# ANET3D-ISP-Adapter.net
KiCad netlist of a schematic drawn in EAGLE
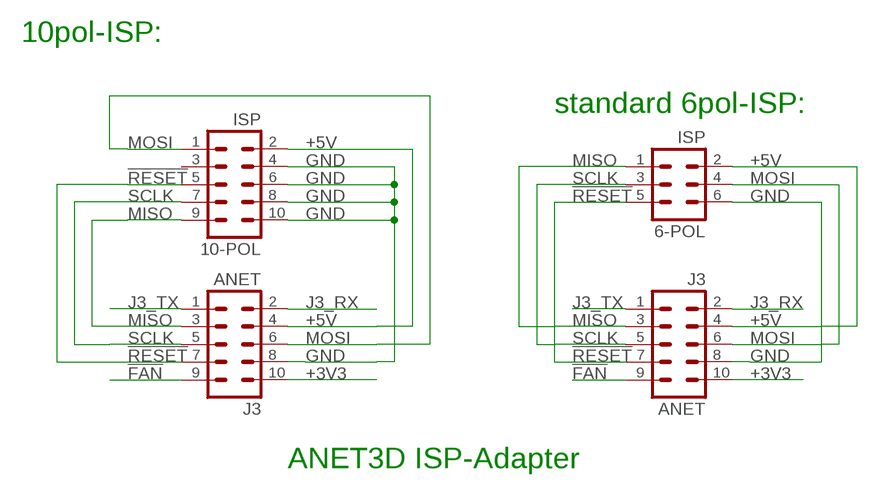
[diagram p0: schematic, sheet 1]

(export (version "E")
  (design (tool "Eeschema 10.0.6"))
  (components
    (comp (ref "6-POL")
      (value "ISP")
      (footprint "eagle-import:ML6")
      (libsource (lib "eagle-import") (part "ML6"))
    )
    (comp (ref "10-POL")
      (value "ISP")
      (footprint "eagle-import:ML10")
      (libsource (lib "eagle-import") (part "ML10"))
    )
    (comp (ref "ANET")
      (value "J3")
      (footprint "eagle-import:ML10")
      (libsource (lib "eagle-import") (part "ML10"))
    )
    (comp (ref "J3")
      (value "ANET")
      (footprint "eagle-import:ML10")
      (libsource (lib "eagle-import") (part "ML10"))
    )
  )
  (nets
    (net (code "1") (name "/+3V3") (class "Default")
      (node (ref "ANET") (pin "10") (pinfunction "10_10") (pintype "passive"))
      (node (ref "J3") (pin "10") (pinfunction "10_10") (pintype "passive"))
    )
    (net (code "2") (name "/+5V") (class "Default")
      (node (ref "10-POL") (pin "2") (pinfunction "2_2") (pintype "passive"))
      (node (ref "6-POL") (pin "2") (pinfunction "2_2") (pintype "passive"))
      (node (ref "ANET") (pin "4") (pinfunction "4_4") (pintype "passive"))
      (node (ref "J3") (pin "4") (pinfunction "4_4") (pintype "passive"))
    )
    (net (code "3") (name "/GND") (class "Default")
      (node (ref "10-POL") (pin "10") (pinfunction "10_10") (pintype "passive"))
      (node (ref "10-POL") (pin "4") (pinfunction "4_4") (pintype "passive"))
      (node (ref "10-POL") (pin "6") (pinfunction "6_6") (pintype "passive"))
      (node (ref "10-POL") (pin "8") (pinfunction "8_8") (pintype "passive"))
      (node (ref "6-POL") (pin "6") (pinfunction "6_6") (pintype "passive"))
      (node (ref "ANET") (pin "8") (pinfunction "8_8") (pintype "passive"))
      (node (ref "J3") (pin "8") (pinfunction "8_8") (pintype "passive"))
    )
    (net (code "4") (name "/J3_RX") (class "Default")
      (node (ref "ANET") (pin "2") (pinfunction "2_2") (pintype "passive"))
      (node (ref "J3") (pin "2") (pinfunction "2_2") (pintype "passive"))
    )
    (net (code "5") (name "/J3_TX") (class "Default")
      (node (ref "ANET") (pin "1") (pinfunction "1_1") (pintype "passive"))
      (node (ref "J3") (pin "1") (pinfunction "1_1") (pintype "passive"))
    )
    (net (code "6") (name "/MISO") (class "Default")
      (node (ref "10-POL") (pin "9") (pinfunction "9_9") (pintype "passive"))
      (node (ref "6-POL") (pin "1") (pinfunction "1_1") (pintype "passive"))
      (node (ref "ANET") (pin "3") (pinfunction "3_3") (pintype "passive"))
      (node (ref "J3") (pin "3") (pinfunction "3_3") (pintype "passive"))
    )
    (net (code "7") (name "/MOSI") (class "Default")
      (node (ref "10-POL") (pin "1") (pinfunction "1_1") (pintype "passive"))
      (node (ref "6-POL") (pin "4") (pinfunction "4_4") (pintype "passive"))
      (node (ref "ANET") (pin "6") (pinfunction "6_6") (pintype "passive"))
      (node (ref "J3") (pin "6") (pinfunction "6_6") (pintype "passive"))
    )
    (net (code "8") (name "/SCLK") (class "Default")
      (node (ref "10-POL") (pin "7") (pinfunction "7_7") (pintype "passive"))
      (node (ref "6-POL") (pin "3") (pinfunction "3_3") (pintype "passive"))
      (node (ref "ANET") (pin "5") (pinfunction "5_5") (pintype "passive"))
      (node (ref "J3") (pin "5") (pinfunction "5_5") (pintype "passive"))
    )
    (net (code "9") (name "/~{FAN}") (class "Default")
      (node (ref "ANET") (pin "9") (pinfunction "9_9") (pintype "passive"))
      (node (ref "J3") (pin "9") (pinfunction "9_9") (pintype "passive"))
    )
    (net (code "10") (name "/~{RESET}") (class "Default")
      (node (ref "10-POL") (pin "5") (pinfunction "5_5") (pintype "passive"))
      (node (ref "6-POL") (pin "5") (pinfunction "5_5") (pintype "passive"))
      (node (ref "ANET") (pin "7") (pinfunction "7_7") (pintype "passive"))
      (node (ref "J3") (pin "7") (pinfunction "7_7") (pintype "passive"))
    )
    (net (code "11") (name "unconnected-(10-POL-Pad3)") (class "Default")
      (node (ref "10-POL") (pin "3") (pinfunction "3_3") (pintype "passive"))
    )
  )
)
